# Power.net
KiCad netlist of a schematic drawn in Altium Designer
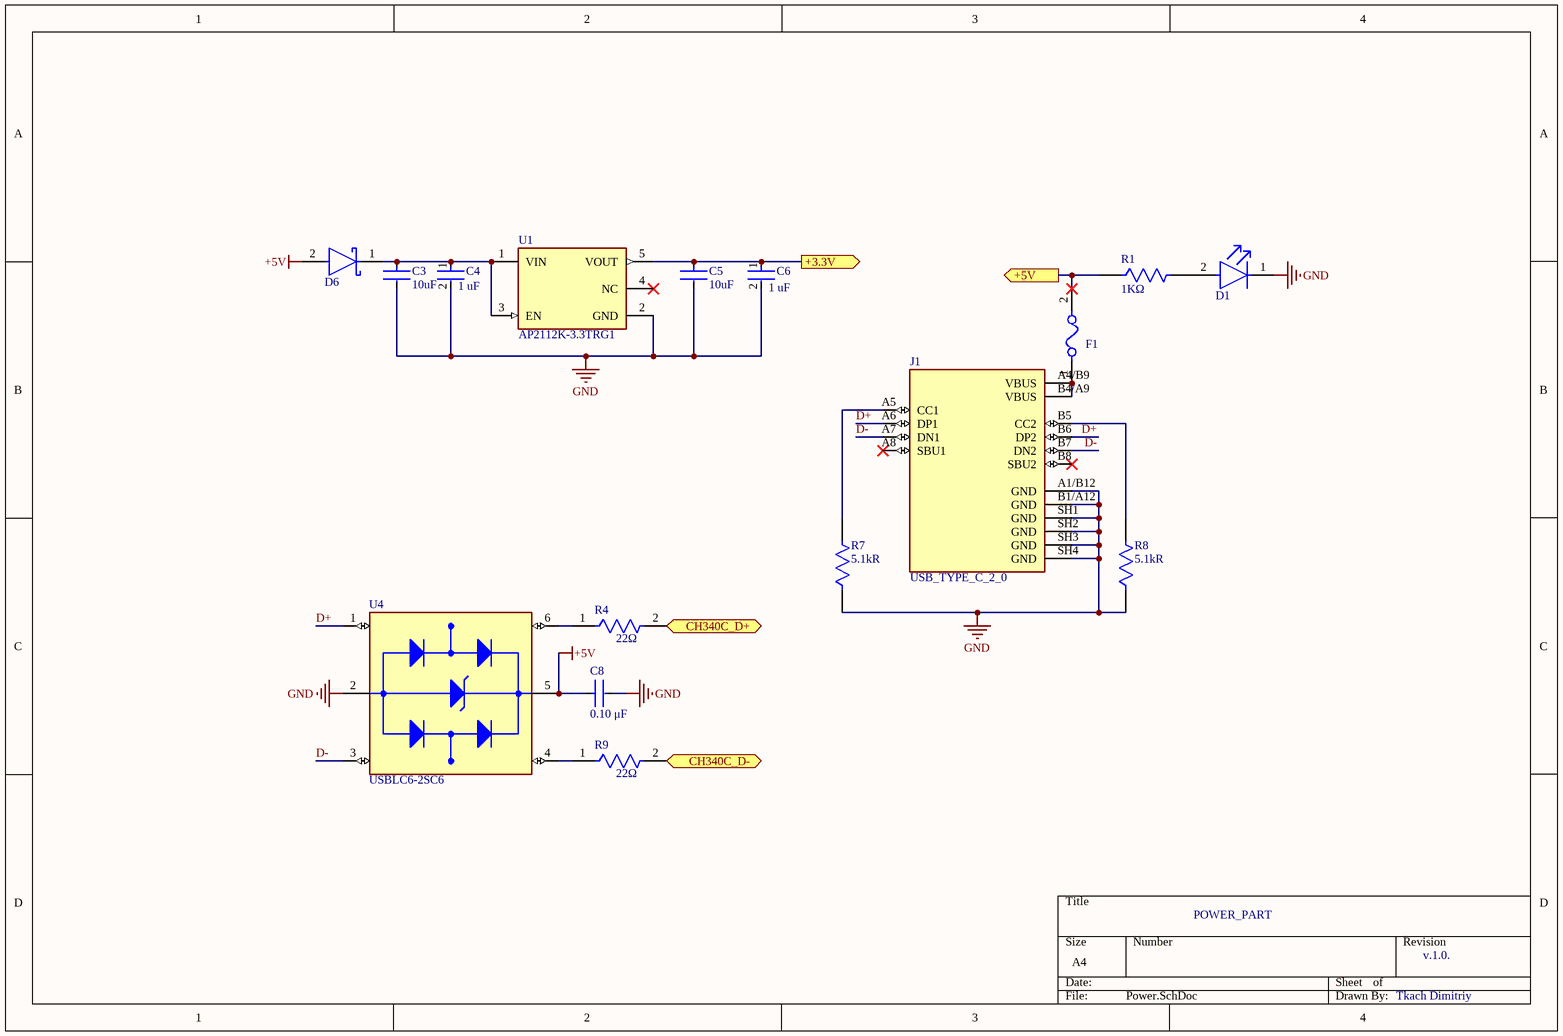
[diagram p0: Power.SchDoc]

(export (version "E")
  (design (tool "Eeschema 10.0.6"))
  (components
    (comp (ref "C3")
      (value "CGA5L1X7R1C106KT0Y0N")
      (footprint "CAPC3216X18M")
      (description "Cap Ceramic 10uF 16V X7R 10% Pad SMD 1206 +125°C Automotive T/R")
      (fields (field (name "CAPACITY") "10uF"))
      (libsource (lib "Internal_Lib_Thermostat_STM8") (part "CMP-08246-001386-1"))
    )
    (comp (ref "C4")
      (value "1 uF")
      (footprint "CAPC3216X18M")
      (description "CC1206 1 uF X7R 10.00%16 V")
      (fields (field (name "TOLERANCE") "0.1") (field (name "MANUFACTURER") "Yageo"))
      (libsource (lib "Internal_Lib_Thermostat_STM8") (part "CMP-03422-001151-1"))
    )
    (comp (ref "C5")
      (value "CGA5L1X7R1C106KT0Y0N")
      (footprint "CAPC3216X18M")
      (description "Cap Ceramic 10uF 16V X7R 10% Pad SMD 1206 +125°C Automotive T/R")
      (fields (field (name "CAPACITY") "10uF"))
      (libsource (lib "Internal_Lib_Thermostat_STM8") (part "CMP-08246-001386-1"))
    )
    (comp (ref "C6")
      (value "1 uF")
      (footprint "CAPC3216X18M")
      (description "CC1206 1 uF X7R 10.00%16 V")
      (fields (field (name "TOLERANCE") "0.1") (field (name "MANUFACTURER") "Yageo"))
      (libsource (lib "Internal_Lib_Thermostat_STM8") (part "CMP-03422-001151-1"))
    )
    (comp (ref "C8")
      (value "C1206C104K5RACAUTO")
      (footprint "CAPC3216X18M")
      (description "CAP CER 0.1UF 50V X7R 1206")
      (fields
        (field (name "MANUFACTURER") "KEMET")
        (field (name "OCTOPART") "https://octopart.com/c1206c104k5racauto-kemet-12595586")
        (field (name "CAPACITANCE") "0.10 μF")
      )
      (libsource (lib "Internal_Lib_Thermostat_STM8") (part "CMP-03020-005759-1"))
    )
    (comp (ref "D1")
      (value "LTST-C150KRKT")
      (footprint "FP-LTST-C150KRKT-MFG")
      (description "LED RED CLEAR 1206 SMD")
      (libsource (lib "Internal_Lib_Thermostat_STM8") (part "8706943c75ba83719d021d2fdc84c58"))
    )
    (comp (ref "D6")
      (value "1N5819HW-7-F")
      (footprint "FP-SOD123-MFG")
      (description "DIODE SCHOTTKY 40V 1A SOD123")
      (libsource (lib "Internal_Lib_Thermostat_STM8") (part "CMP-0303-00003-3"))
    )
    (comp (ref "F1")
      (value "MF-NSMF050-2")
      (footprint "RESC3216X06M")
      (description "PTC RESET FUSE 13.2V 500MA 1206")
      (fields
        (field (name "MANUFACTURER") "Bourns")
        (field (name "OCTOPART") "https://octopart.com/mf-nsmf050-2-bourns-34532")
      )
      (libsource (lib "Internal_Lib_Thermostat_STM8") (part "CMP-07400-000036-1"))
    )
    (comp (ref "J1")
      (value "USB_TYPE_C_2_0")
      (footprint "USB Type-C 16Pin")
      (fields (field (name "MP") "USB4110GFA") (field (name "MF") "Global Connector Technology"))
      (libsource (lib "Internal_Lib_Thermostat_STM8") (part "USB_CMP-002-00072-1"))
    )
    (comp (ref "R1")
      (value "1KΩ")
      (footprint "RESC3216X06M")
      (description "CRGCQ1206 1KΩ 0.25W 1% ±100ppm/°C 200V")
      (fields
        (field (name "MANUFACTURER") "TE Connectivity")
        (field (name "MANUFACTURER PART NUMBER") "CRGCQ1206F1K0")
      )
      (libsource (lib "Internal_Lib_Thermostat_STM8") (part "CMP-03211-006592-1"))
    )
    (comp (ref "R4")
      (value "SR0603FR-7T22RL")
      (footprint "RESC3216X06M")
      (description "RES 22 OHM 1% 1/4W 0603")
      (fields
        (field (name "RESISTANCE") "22Ω")
        (field (name "MANUFACTURER") "Yageo")
        (field (name "OCTOPART") "https://octopart.com/sr0603fr-7t22rl-yageo-91478080")
      )
      (libsource (lib "Internal_Lib_Thermostat_STM8") (part "CMP-03412-021889-1"))
    )
    (comp (ref "R7")
      (value "ESR18EZPF5101")
      (footprint "RESC3216X06M")
      (description "5.1kΩ ±1% 0.5W 1206 Anti-Surge Chip Resistor AEC-Q200")
      (fields (field (name "TOLERANCE") "1%") (field (name "RESISTANCE") "5.1kR"))
      (libsource (lib "Internal_Lib_Thermostat_STM8") (part "CMP-08839-028234-1"))
    )
    (comp (ref "R8")
      (value "ESR18EZPF5101")
      (footprint "RESC3216X06M")
      (description "5.1kΩ ±1% 0.5W 1206 Anti-Surge Chip Resistor AEC-Q200")
      (fields (field (name "TOLERANCE") "1%") (field (name "RESISTANCE") "5.1kR"))
      (libsource (lib "Internal_Lib_Thermostat_STM8") (part "CMP-08839-028234-1"))
    )
    (comp (ref "R9")
      (value "SR0603FR-7T22RL")
      (footprint "RESC3216X06M")
      (description "RES 22 OHM 1% 1/4W 0603")
      (fields
        (field (name "RESISTANCE") "22Ω")
        (field (name "MANUFACTURER") "Yageo")
        (field (name "OCTOPART") "https://octopart.com/sr0603fr-7t22rl-yageo-91478080")
      )
      (libsource (lib "Internal_Lib_Thermostat_STM8") (part "CMP-03412-021889-1"))
    )
    (comp (ref "U1")
      (value "AP2112K-3.3TRG1")
      (footprint "FP-SOT25-IPC_A")
      (description "IC REG LINEAR 3.3V 600MA SOT25")
      (libsource (lib "Internal_Lib_Thermostat_STM8") (part "CMP-12756-000035-1"))
    )
    (comp (ref "U4")
      (value "USBLC6-2SC6")
      (footprint "SOT95P280X145-6N")
      (description "17V Clamp 5A (8/20Âµs) Ipp Tvs Diode Surface Mount SOT-23-6")
      (fields (field (name "MF") "STMicroelectronics"))
      (libsource (lib "Internal_Lib_Thermostat_STM8") (part "USBLC6-2SC6"))
    )
  )
  (nets
    (net (code "1") (name "+5V") (class "Default")
      (node (ref "C8") (pin "1") (pinfunction "1_1") (pintype "passive"))
      (node (ref "D6") (pin "2") (pinfunction "A_2") (pintype "passive"))
      (node (ref "F1") (pin "2") (pinfunction "2_2") (pintype "passive"))
      (node (ref "R1") (pin "1") (pinfunction "1_1") (pintype "passive"))
      (node (ref "U4") (pin "5") (pinfunction "VBUS_5") (pintype "power_in"))
    )
    (net (code "2") (name "/+3.3V") (class "Default")
      (node (ref "C5") (pin "1") (pinfunction "1_1") (pintype "passive"))
      (node (ref "C6") (pin "1") (pinfunction "1_1") (pintype "passive"))
      (node (ref "U1") (pin "5") (pinfunction "VOUT_5") (pintype "output"))
    )
    (net (code "3") (name "/CH340C_D+") (class "Default")
      (node (ref "R4") (pin "2") (pinfunction "2_2") (pintype "passive"))
    )
    (net (code "4") (name "/CH340C_D-") (class "Default")
      (node (ref "R9") (pin "2") (pinfunction "2_2") (pintype "passive"))
    )
    (net (code "5") (name "/D+") (class "Default")
      (node (ref "J1") (pin "A6") (pinfunction "DP1_A6") (pintype "bidirectional"))
      (node (ref "J1") (pin "B6") (pinfunction "DP2_B6") (pintype "bidirectional"))
      (node (ref "U4") (pin "1") (pinfunction "I/O1_IN_1") (pintype "bidirectional"))
    )
    (net (code "6") (name "/D-") (class "Default")
      (node (ref "J1") (pin "A7") (pinfunction "DN1_A7") (pintype "bidirectional"))
      (node (ref "J1") (pin "B7") (pinfunction "DN2_B7") (pintype "bidirectional"))
      (node (ref "U4") (pin "3") (pinfunction "I/O2_IN_3") (pintype "bidirectional"))
    )
    (net (code "7") (name "GND") (class "Default")
      (node (ref "C3") (pin "2") (pinfunction "2_2") (pintype "passive"))
      (node (ref "C4") (pin "2") (pinfunction "2_2") (pintype "passive"))
      (node (ref "C5") (pin "2") (pinfunction "2_2") (pintype "passive"))
      (node (ref "C6") (pin "2") (pinfunction "2_2") (pintype "passive"))
      (node (ref "C8") (pin "2") (pinfunction "2_2") (pintype "passive"))
      (node (ref "D1") (pin "1") (pinfunction "C_1") (pintype "passive"))
      (node (ref "J1") (pin "A1/B12") (pinfunction "GND_A1/B12") (pintype "power_in"))
      (node (ref "J1") (pin "B1/A12") (pinfunction "GND_B1/A12") (pintype "power_in"))
      (node (ref "J1") (pin "SH1") (pinfunction "GND_SH1") (pintype "power_in"))
      (node (ref "J1") (pin "SH2") (pinfunction "GND_SH2") (pintype "power_in"))
      (node (ref "J1") (pin "SH3") (pinfunction "GND_SH3") (pintype "power_in"))
      (node (ref "J1") (pin "SH4") (pinfunction "GND_SH4") (pintype "power_in"))
      (node (ref "R7") (pin "1") (pinfunction "1_1") (pintype "passive"))
      (node (ref "R8") (pin "1") (pinfunction "1_1") (pintype "passive"))
      (node (ref "U1") (pin "2") (pinfunction "GND_2") (pintype "power_in"))
      (node (ref "U4") (pin "2") (pinfunction "GND_2") (pintype "power_in"))
    )
    (net (code "8") (name "Net-(D1-A)") (class "Default")
      (node (ref "D1") (pin "2") (pinfunction "A_2") (pintype "passive"))
      (node (ref "R1") (pin "2") (pinfunction "2_2") (pintype "passive"))
    )
    (net (code "9") (name "Net-(D6-C)") (class "Default")
      (node (ref "C3") (pin "1") (pinfunction "1_1") (pintype "passive"))
      (node (ref "C4") (pin "1") (pinfunction "1_1") (pintype "passive"))
      (node (ref "D6") (pin "1") (pinfunction "C_1") (pintype "passive"))
      (node (ref "U1") (pin "1") (pinfunction "VIN_1") (pintype "power_in"))
      (node (ref "U1") (pin "3") (pinfunction "EN_3") (pintype "input"))
    )
    (net (code "10") (name "Net-(F1-Pad1)") (class "Default")
      (node (ref "F1") (pin "1") (pinfunction "1_1") (pintype "passive"))
      (node (ref "J1") (pin "A4/B9") (pinfunction "VBUS_A4/B9") (pintype "power_in"))
      (node (ref "J1") (pin "B4/A9") (pinfunction "VBUS_B4/A9") (pintype "power_in"))
    )
    (net (code "11") (name "Net-(J1-CC1)") (class "Default")
      (node (ref "J1") (pin "A5") (pinfunction "CC1_A5") (pintype "bidirectional"))
      (node (ref "R7") (pin "2") (pinfunction "2_2") (pintype "passive"))
    )
    (net (code "12") (name "Net-(J1-CC2)") (class "Default")
      (node (ref "J1") (pin "B5") (pinfunction "CC2_B5") (pintype "bidirectional"))
      (node (ref "R8") (pin "2") (pinfunction "2_2") (pintype "passive"))
    )
    (net (code "13") (name "Net-(U4-I{slash}O1_OUT)") (class "Default")
      (node (ref "R4") (pin "1") (pinfunction "1_1") (pintype "passive"))
      (node (ref "U4") (pin "6") (pinfunction "I/O1_OUT_6") (pintype "bidirectional"))
    )
    (net (code "14") (name "Net-(U4-I{slash}O2_OUT)") (class "Default")
      (node (ref "R9") (pin "1") (pinfunction "1_1") (pintype "passive"))
      (node (ref "U4") (pin "4") (pinfunction "I/O2_OUT_4") (pintype "bidirectional"))
    )
    (net (code "15") (name "unconnected-(J1-SBU1-PadA8)") (class "Default")
      (node (ref "J1") (pin "A8") (pinfunction "SBU1_A8") (pintype "bidirectional+no_connect"))
    )
    (net (code "16") (name "unconnected-(J1-SBU2-PadB8)") (class "Default")
      (node (ref "J1") (pin "B8") (pinfunction "SBU2_B8") (pintype "bidirectional+no_connect"))
    )
    (net (code "17") (name "unconnected-(U1-NC-Pad4)") (class "Default")
      (node (ref "U1") (pin "4") (pinfunction "NC_4") (pintype "passive+no_connect"))
    )
  )
)
